# PR9018.net
KiCad netlist of a schematic drawn in EAGLE
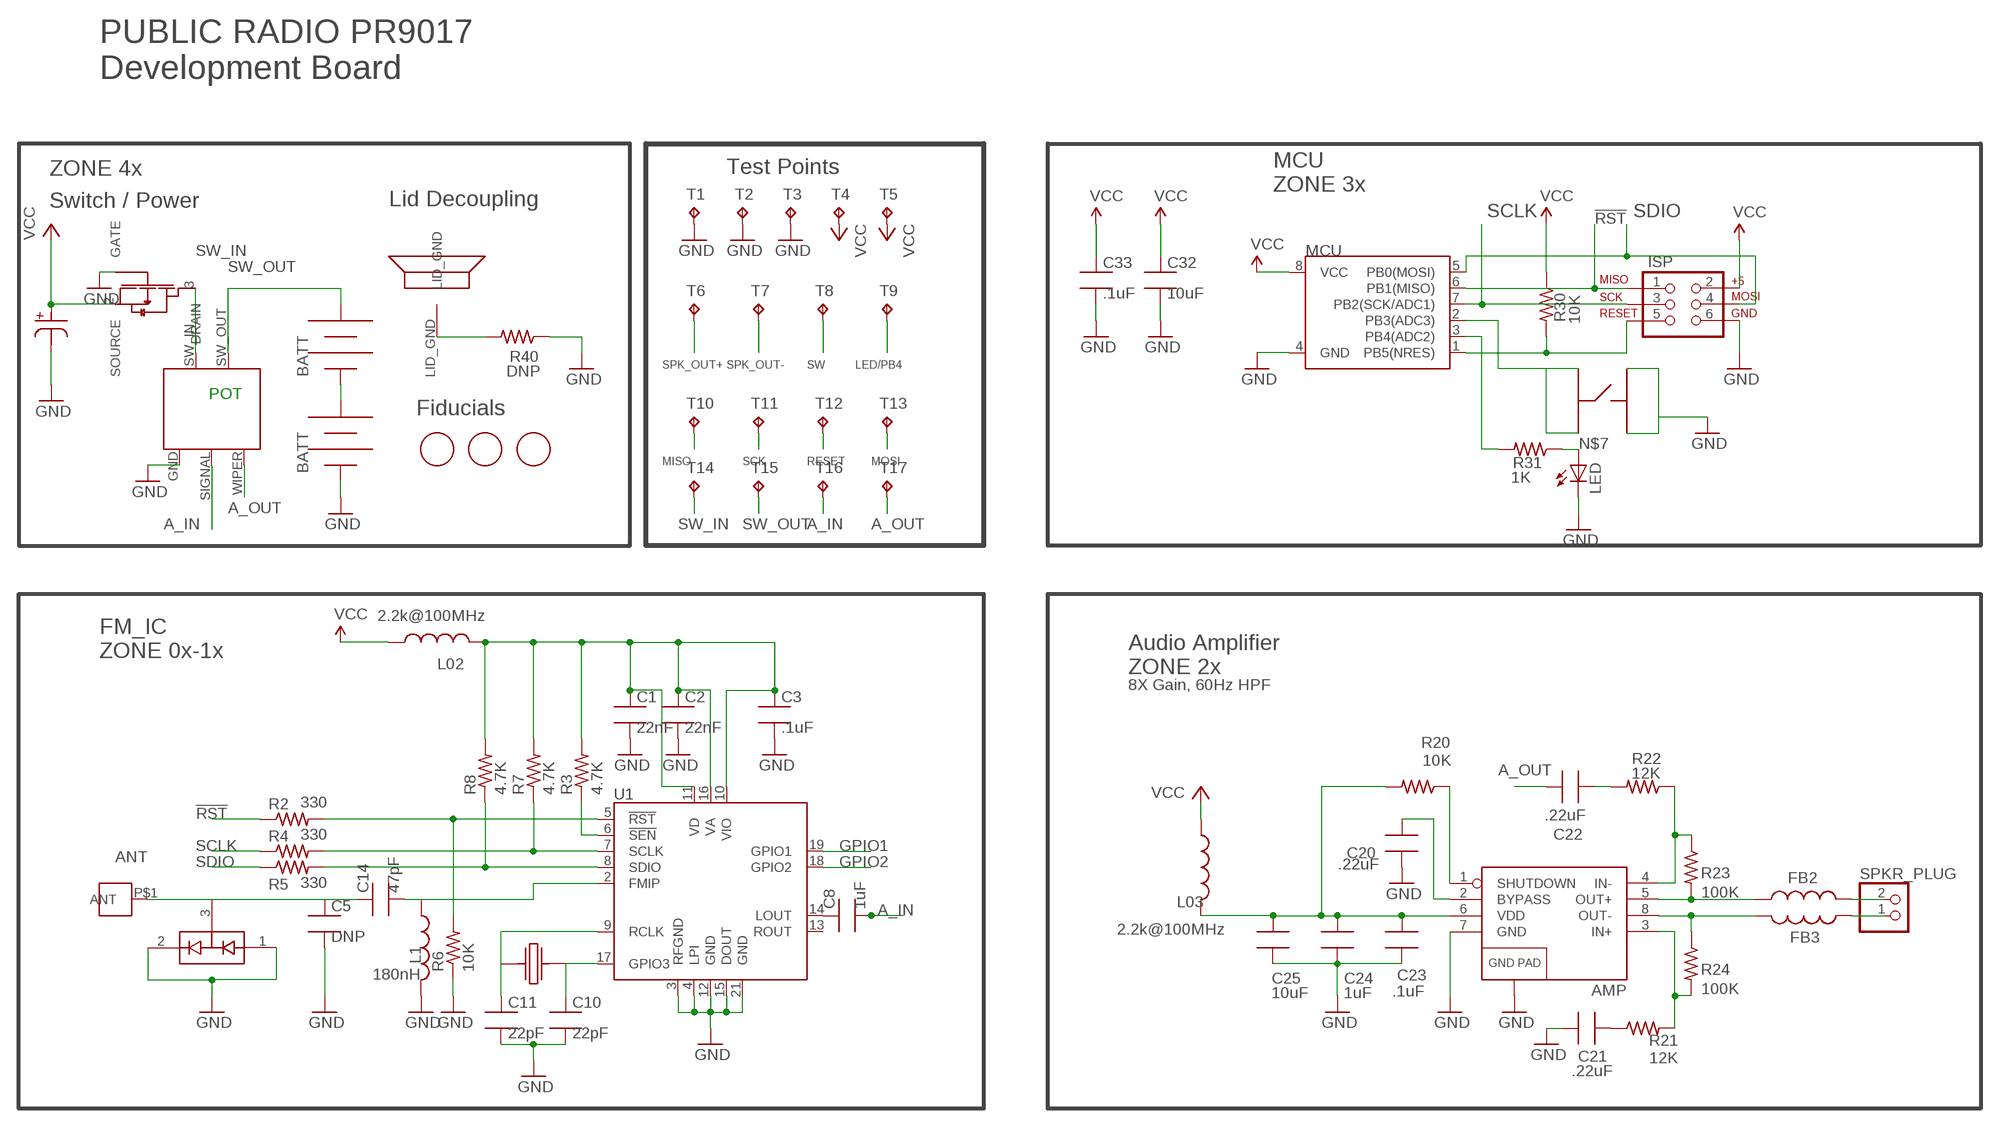
[diagram p0: schematic, sheet 1]

(export (version "E")
  (design (tool "Eeschema 10.0.6"))
  (components
    (comp (ref "AMP")
      (value "TPA6203A1")
      (footprint "eagle-import:8-MSOP")
      (libsource (lib "eagle-import") (part "TPA6203A1"))
    )
    (comp (ref "ANT_MOUNT")
      (value "DNP")
      (footprint "eagle-import:M3_BOLT_HOLE")
      (libsource (lib "eagle-import") (part "M3_SCREW_POST"))
    )
    (comp (ref "C1")
      (value "22nF")
      (footprint "eagle-import:0603_CPL")
      (fields
        (field (name "MFG_PN") "CL10B223KB8NNNC")
        (field (name "TOL") "10%")
        (field (name "VOLTAGE") "16V")
      )
      (libsource (lib "eagle-import") (part "C_SMT_0603_CPL"))
    )
    (comp (ref "C2")
      (value "22nF")
      (footprint "eagle-import:0603_CPL")
      (fields
        (field (name "MFG_PN") "CL10B223KB8NNNC")
        (field (name "TOL") "10%")
        (field (name "VOLTAGE") "16V")
      )
      (libsource (lib "eagle-import") (part "C_SMT_0603_CPL"))
    )
    (comp (ref "C3")
      (value ".1uF")
      (footprint "eagle-import:0603_CPL")
      (fields
        (field (name "MFG_PN") "CL10B104KB8SFNC")
        (field (name "TOL") "10%")
        (field (name "VOLTAGE") "16V")
      )
      (libsource (lib "eagle-import") (part "C_SMT_0603_CPL"))
    )
    (comp (ref "C5")
      (value "DNP")
      (footprint "eagle-import:0603_CPL")
      (fields (field (name "MFG_PN") "DNP") (field (name "TOL") "2%") (field (name "VOLTAGE") "50V"))
      (libsource (lib "eagle-import") (part "C_SMT_0603_CPL"))
    )
    (comp (ref "C8")
      (value "1uF")
      (footprint "eagle-import:0603_CPL")
      (fields
        (field (name "MFG_PN") "CL10B105KP8NNNC")
        (field (name "TOL") "10%")
        (field (name "VOLTAGE") "10V")
      )
      (libsource (lib "eagle-import") (part "C_SMT_0603_CPL"))
    )
    (comp (ref "C10")
      (value "22pF")
      (footprint "eagle-import:0603_CPL")
      (fields
        (field (name "MFG_PN") "C1608C0G1H220J080AA")
        (field (name "TOL") "5%")
        (field (name "VOLTAGE") "50V")
      )
      (libsource (lib "eagle-import") (part "C_SMT_0603_CPL"))
    )
    (comp (ref "C11")
      (value "22pF")
      (footprint "eagle-import:0603_CPL")
      (fields
        (field (name "MFG_PN") "C1608C0G1H220J080AA")
        (field (name "TOL") "5%")
        (field (name "VOLTAGE") "50V")
      )
      (libsource (lib "eagle-import") (part "C_SMT_0603_CPL"))
    )
    (comp (ref "C14")
      (value "47pF")
      (footprint "eagle-import:0603_CPL")
      (fields
        (field (name "MFG_PN") "CL10C470JB8NCNC")
        (field (name "TOL") "5%")
        (field (name "VOLTAGE") "50V")
      )
      (libsource (lib "eagle-import") (part "C_SMT_0603_CPL"))
    )
    (comp (ref "C20")
      (value ".22uF")
      (footprint "eagle-import:0603_CPL")
      (fields
        (field (name "MFG_PN") "C1608X7R1C224K080AC")
        (field (name "TOL") "10%")
        (field (name "VOLTAGE") "16V")
      )
      (libsource (lib "eagle-import") (part "C_SMT_0603_CPL"))
    )
    (comp (ref "C21")
      (value ".22uF")
      (footprint "eagle-import:0603_CPL")
      (fields
        (field (name "MFG_PN") "C1608X7R1C224K080AC")
        (field (name "TOL") "10%")
        (field (name "VOLTAGE") "16V")
      )
      (libsource (lib "eagle-import") (part "C_SMT_0603_CPL"))
    )
    (comp (ref "C22")
      (value ".22uF")
      (footprint "eagle-import:0603_CPL")
      (fields
        (field (name "MFG_PN") "C1608X7R1C224K080AC")
        (field (name "TOL") "10%")
        (field (name "VOLTAGE") "16V")
      )
      (libsource (lib "eagle-import") (part "C_SMT_0603_CPL"))
    )
    (comp (ref "C23")
      (value ".1uF")
      (footprint "eagle-import:0603_CPL")
      (fields
        (field (name "MFG_PN") "CL10B104KB8SFNC")
        (field (name "TOL") "10%")
        (field (name "VOLTAGE") "16V")
      )
      (libsource (lib "eagle-import") (part "C_SMT_0603_CPL"))
    )
    (comp (ref "C24")
      (value "1uF")
      (footprint "eagle-import:0603_CPL")
      (fields
        (field (name "MFG_PN") "CL10B105KP8NNNC")
        (field (name "TOL") "10%")
        (field (name "VOLTAGE") "10V")
      )
      (libsource (lib "eagle-import") (part "C_SMT_0603_CPL"))
    )
    (comp (ref "C25")
      (value "10uF")
      (footprint "eagle-import:0603_CPL")
      (fields
        (field (name "MFG_PN") "CL10A106MQ8NNNC")
        (field (name "TOL") "20%")
        (field (name "VOLTAGE") "6.3V")
      )
      (libsource (lib "eagle-import") (part "C_SMT_0603_CPL"))
    )
    (comp (ref "C32")
      (value "10uF")
      (footprint "eagle-import:0603_CPL")
      (fields
        (field (name "MFG_PN") "CL10A106MQ8NNNC")
        (field (name "TOL") "20%")
        (field (name "VOLTAGE") "6.3V")
      )
      (libsource (lib "eagle-import") (part "C_SMT_0603_CPL"))
    )
    (comp (ref "C33")
      (value ".1uF")
      (footprint "eagle-import:0603_CPL")
      (fields
        (field (name "MFG_PN") "CL10B104KB8SFNC")
        (field (name "TOL") "10%")
        (field (name "VOLTAGE") "16V")
      )
      (libsource (lib "eagle-import") (part "C_SMT_0603_CPL"))
    )
    (comp (ref "C40")
      (value "220uF")
      (footprint "eagle-import:NICHICON_UD_63")
      (fields (field (name "TOL") "20%") (field (name "VOLTAGE") "16V"))
      (libsource (lib "eagle-import") (part "NICHICON_SERIESUD"))
    )
    (comp (ref "D1")
      (value "BAV99")
      (footprint "eagle-import:SOT23_CPL")
      (fields (field (name "MFG_PN") "BAV99,215"))
      (libsource (lib "eagle-import") (part "BAV99"))
    )
    (comp (ref "FB2")
      (value "L_SMT_0805_ADAFRUIT")
      (footprint "eagle-import:0805_ADAFRUIT")
      (fields
        (field (name "CURRENT") "2A")
        (field (name "DCR") "45m")
        (field (name "MFG_PN") "HI0805R800R-10")
      )
      (libsource (lib "eagle-import") (part "L_SMT_0805_ADAFRUIT"))
    )
    (comp (ref "FB3")
      (value "L_SMT_0805_ADAFRUIT")
      (footprint "eagle-import:0805_ADAFRUIT")
      (fields
        (field (name "CURRENT") "2A")
        (field (name "DCR") "45m")
        (field (name "MFG_PN") "HI0805R800R-10")
      )
      (libsource (lib "eagle-import") (part "L_SMT_0805_ADAFRUIT"))
    )
    (comp (ref "FET1")
      (value "AO3435")
      (footprint "eagle-import:SOT23_CPL")
      (fields (field (name "MFG_PN") "AO3435"))
      (libsource (lib "eagle-import") (part "AO3435"))
    )
    (comp (ref "ISP")
      (value "AVR_SPI_PRG_6NS")
      (footprint "eagle-import:2X3-NS")
      (libsource (lib "eagle-import") (part "AVR_SPI_PRG_6NS"))
    )
    (comp (ref "JP5")
      (value "BK-92_MPD_AA_BATT_CLIP")
      (footprint "eagle-import:BK92_AA_BATT")
      (libsource (lib "eagle-import") (part "BK-92_MPD_AA_BATT_CLIP"))
    )
    (comp (ref "JP6")
      (value "BK-92_MPD_AA_BATT_CLIP")
      (footprint "eagle-import:BK92_AA_BATT")
      (libsource (lib "eagle-import") (part "BK-92_MPD_AA_BATT_CLIP"))
    )
    (comp (ref "L1")
      (value "180nH")
      (footprint "eagle-import:0805_ADAFRUIT")
      (fields
        (field (name "CURRENT") "400mA")
        (field (name "DCR") "640m")
        (field (name "MFG_PN") "AISC-0805-R18J-T")
        (field (name "TOL") "5%")
      )
      (libsource (lib "eagle-import") (part "L_SMT_0805_ADAFRUIT"))
    )
    (comp (ref "L02")
      (value "2.2k@100MHz")
      (footprint "eagle-import:0603_CPL")
      (fields
        (field (name "CURRENT") "150mA")
        (field (name "DCR") "2.3")
        (field (name "MFG_PN") "HZ0603A222R-10")
      )
      (libsource (lib "eagle-import") (part "L_SMT_0603_CPL"))
    )
    (comp (ref "L03")
      (value "2.2k@100MHz")
      (footprint "eagle-import:0603_CPL")
      (fields
        (field (name "CURRENT") "150mA")
        (field (name "DCR") "2.3")
        (field (name "MFG_PN") "HZ0603A222R-10")
      )
      (libsource (lib "eagle-import") (part "L_SMT_0603_CPL"))
    )
    (comp (ref "LED")
      (value "LED")
      (footprint "eagle-import:0603_CPL")
      (fields (field (name "MFG_PN") "LY R976-PS-36"))
      (libsource (lib "eagle-import") (part "LED"))
    )
    (comp (ref "MARK1")
      (value "FIDUCIAL")
      (footprint "eagle-import:FIDUCIAL_1MM")
      (libsource (lib "eagle-import") (part "FIDUCIAL"))
    )
    (comp (ref "MARK2")
      (value "FIDUCIAL")
      (footprint "eagle-import:FIDUCIAL_1MM")
      (libsource (lib "eagle-import") (part "FIDUCIAL"))
    )
    (comp (ref "MARK3")
      (value "FIDUCIAL")
      (footprint "eagle-import:FIDUCIAL_1MM")
      (libsource (lib "eagle-import") (part "FIDUCIAL"))
    )
    (comp (ref "MCU")
      (value "ATTINY45TINY45-20-SMT")
      (footprint "eagle-import:8-SOIC")
      (libsource (lib "eagle-import") (part "ATTINY45TINY45-20-SMT"))
    )
    (comp (ref "R1")
      (value "RV170SF_TAIWANA_POT_SW")
      (footprint "eagle-import:RV170SF_SW_POT")
      (libsource (lib "eagle-import") (part "RV170SF_TAIWANA_POT_SW"))
    )
    (comp (ref "R2")
      (value "330")
      (footprint "eagle-import:0603_CPL")
      (fields (field (name "MFG_PN") "MCR03ERTJ331") (field (name "POWER") "1/10W") (field (name "TOL") "5%"))
      (libsource (lib "eagle-import") (part "R_SMT_R0603_CPL"))
    )
    (comp (ref "R3")
      (value "4.7K")
      (footprint "eagle-import:0603_CPL")
      (fields
        (field (name "MFG_PN") "ERJ-3EKF4701V")
        (field (name "POWER") "1/10W")
        (field (name "TOL") "1%")
      )
      (libsource (lib "eagle-import") (part "R_SMT_R0603_CPL"))
    )
    (comp (ref "R4")
      (value "330")
      (footprint "eagle-import:0603_CPL")
      (fields (field (name "MFG_PN") "MCR03ERTJ331") (field (name "POWER") "1/10W") (field (name "TOL") "5%"))
      (libsource (lib "eagle-import") (part "R_SMT_R0603_CPL"))
    )
    (comp (ref "R5")
      (value "330")
      (footprint "eagle-import:0603_CPL")
      (fields (field (name "MFG_PN") "MCR03ERTJ331") (field (name "POWER") "1/10W") (field (name "TOL") "5%"))
      (libsource (lib "eagle-import") (part "R_SMT_R0603_CPL"))
    )
    (comp (ref "R6")
      (value "10K")
      (footprint "eagle-import:0603_CPL")
      (fields
        (field (name "MFG_PN") "ERJ-3GEYJ103V")
        (field (name "POWER") "1/10W")
        (field (name "TOL") "5%")
      )
      (libsource (lib "eagle-import") (part "R_SMT_R0603_CPL"))
    )
    (comp (ref "R7")
      (value "4.7K")
      (footprint "eagle-import:0603_CPL")
      (fields
        (field (name "MFG_PN") "ERJ-3EKF4701V")
        (field (name "POWER") "1/10W")
        (field (name "TOL") "1%")
      )
      (libsource (lib "eagle-import") (part "R_SMT_R0603_CPL"))
    )
    (comp (ref "R8")
      (value "4.7K")
      (footprint "eagle-import:0603_CPL")
      (fields
        (field (name "MFG_PN") "ERJ-3EKF4701V")
        (field (name "POWER") "1/10W")
        (field (name "TOL") "1%")
      )
      (libsource (lib "eagle-import") (part "R_SMT_R0603_CPL"))
    )
    (comp (ref "R20")
      (value "10K")
      (footprint "eagle-import:0603_CPL")
      (fields
        (field (name "MFG_PN") "ERJ-3GEYJ103V")
        (field (name "POWER") "1/10W")
        (field (name "TOL") "5%")
      )
      (libsource (lib "eagle-import") (part "R_SMT_R0603_CPL"))
    )
    (comp (ref "R21")
      (value "12K")
      (footprint "eagle-import:0603_CPL")
      (fields
        (field (name "MFG_PN") "RC0603FR-0712KL")
        (field (name "POWER") "1/10W")
        (field (name "TOL") "1%")
      )
      (libsource (lib "eagle-import") (part "R_SMT_R0603_CPL"))
    )
    (comp (ref "R22")
      (value "12K")
      (footprint "eagle-import:0603_CPL")
      (fields
        (field (name "MFG_PN") "RC0603FR-0712KL")
        (field (name "POWER") "1/10W")
        (field (name "TOL") "1%")
      )
      (libsource (lib "eagle-import") (part "R_SMT_R0603_CPL"))
    )
    (comp (ref "R23")
      (value "100K")
      (footprint "eagle-import:0603_CPL")
      (fields
        (field (name "MFG_PN") "ERJ-3EKF1003V")
        (field (name "POWER") "1/10W")
        (field (name "TOL") "1%")
      )
      (libsource (lib "eagle-import") (part "R_SMT_R0603_CPL"))
    )
    (comp (ref "R24")
      (value "100K")
      (footprint "eagle-import:0603_CPL")
      (fields
        (field (name "MFG_PN") "ERJ-3EKF1003V")
        (field (name "POWER") "1/10W")
        (field (name "TOL") "1%")
      )
      (libsource (lib "eagle-import") (part "R_SMT_R0603_CPL"))
    )
    (comp (ref "R30")
      (value "10K")
      (footprint "eagle-import:0603_CPL")
      (fields
        (field (name "MFG_PN") "ERJ-3GEYJ103V")
        (field (name "POWER") "1/10W")
        (field (name "TOL") "5%")
      )
      (libsource (lib "eagle-import") (part "R_SMT_R0603_CPL"))
    )
    (comp (ref "R31")
      (value "1K")
      (footprint "eagle-import:0603_CPL")
      (fields
        (field (name "MFG_PN") "ERJ-3EKF1001V")
        (field (name "POWER") "1/10W")
        (field (name "TOL") "1%")
      )
      (libsource (lib "eagle-import") (part "R_SMT_R0603_CPL"))
    )
    (comp (ref "R40")
      (value "DNP")
      (footprint "eagle-import:0603_CPL")
      (fields (field (name "MFG_PN") "ERJ-3GEY0R00V"))
      (libsource (lib "eagle-import") (part "R_SMT_R0603_CPL"))
    )
    (comp (ref "SPKR_PLACE")
      (value "DNP")
      (footprint "eagle-import:PR2023_SPKR_PLACE")
      (libsource (lib "eagle-import") (part "PR2023_SPKR"))
    )
    (comp (ref "SPKR_PLUG")
      (value "JST_2PIN-SMT-RA")
      (footprint "eagle-import:JST-B2B-PH-SM4-TB")
      (libsource (lib "eagle-import") (part "JST_2PIN-SMT-RA"))
    )
    (comp (ref "SW1")
      (value "C&K_PTS645")
      (footprint "eagle-import:C&K_PTS645_SMT")
      (libsource (lib "eagle-import") (part "C&K_PTS645"))
    )
    (comp (ref "T1")
      (value "TPTP20R")
      (footprint "eagle-import:TP20R")
      (libsource (lib "eagle-import") (part "TPTP20R"))
    )
    (comp (ref "T2")
      (value "TPTP20R")
      (footprint "eagle-import:TP20R")
      (libsource (lib "eagle-import") (part "TPTP20R"))
    )
    (comp (ref "T3")
      (value "TPTP20R")
      (footprint "eagle-import:TP20R")
      (libsource (lib "eagle-import") (part "TPTP20R"))
    )
    (comp (ref "T4")
      (value "TPTP20R")
      (footprint "eagle-import:TP20R")
      (libsource (lib "eagle-import") (part "TPTP20R"))
    )
    (comp (ref "T5")
      (value "TPTP20R")
      (footprint "eagle-import:TP20R")
      (libsource (lib "eagle-import") (part "TPTP20R"))
    )
    (comp (ref "T6")
      (value "TPTP20R")
      (footprint "eagle-import:TP20R")
      (libsource (lib "eagle-import") (part "TPTP20R"))
    )
    (comp (ref "T7")
      (value "TPTP20R")
      (footprint "eagle-import:TP20R")
      (libsource (lib "eagle-import") (part "TPTP20R"))
    )
    (comp (ref "T8")
      (value "TPTP20R")
      (footprint "eagle-import:TP20R")
      (libsource (lib "eagle-import") (part "TPTP20R"))
    )
    (comp (ref "T9")
      (value "TPTP20R")
      (footprint "eagle-import:TP20R")
      (libsource (lib "eagle-import") (part "TPTP20R"))
    )
    (comp (ref "T10")
      (value "TPTP20R")
      (footprint "eagle-import:TP20R")
      (libsource (lib "eagle-import") (part "TPTP20R"))
    )
    (comp (ref "T11")
      (value "TPTP20R")
      (footprint "eagle-import:TP20R")
      (libsource (lib "eagle-import") (part "TPTP20R"))
    )
    (comp (ref "T12")
      (value "TPTP20R")
      (footprint "eagle-import:TP20R")
      (libsource (lib "eagle-import") (part "TPTP20R"))
    )
    (comp (ref "T13")
      (value "TPTP20R")
      (footprint "eagle-import:TP20R")
      (libsource (lib "eagle-import") (part "TPTP20R"))
    )
    (comp (ref "T14")
      (value "TPTP20R")
      (footprint "eagle-import:TP20R")
      (libsource (lib "eagle-import") (part "TPTP20R"))
    )
    (comp (ref "T15")
      (value "TPTP20R")
      (footprint "eagle-import:TP20R")
      (libsource (lib "eagle-import") (part "TPTP20R"))
    )
    (comp (ref "T16")
      (value "TPTP20R")
      (footprint "eagle-import:TP20R")
      (libsource (lib "eagle-import") (part "TPTP20R"))
    )
    (comp (ref "T17")
      (value "TPTP20R")
      (footprint "eagle-import:TP20R")
      (libsource (lib "eagle-import") (part "TPTP20R"))
    )
    (comp (ref "U1")
      (value "SI4702-C19-GMR")
      (footprint "eagle-import:SI470X_20_QFN")
      (libsource (lib "eagle-import") (part "SI4702-C19-GMR"))
    )
    (comp (ref "X1")
      (value "ABS25XTAL")
      (footprint "eagle-import:4-SOJ")
      (libsource (lib "eagle-import") (part "ABS25XTAL"))
    )
  )
  (nets
    (net (code "1") (name "/ANT") (class "Default")
      (node (ref "ANT_MOUNT") (pin "P$1") (pinfunction "ANT_P$1") (pintype "bidirectional"))
      (node (ref "C14") (pin "1") (pinfunction "1_1") (pintype "passive"))
      (node (ref "C5") (pin "1") (pinfunction "1_1") (pintype "passive"))
      (node (ref "D1") (pin "3") (pinfunction "COM_3") (pintype "bidirectional"))
    )
    (net (code "2") (name "/A_IN") (class "Default")
      (node (ref "C8") (pin "2") (pinfunction "2_2") (pintype "passive"))
      (node (ref "R1") (pin "SIGNAL") (pinfunction "SIGNAL_SIGNAL") (pintype "bidirectional"))
      (node (ref "T16") (pin "TP") (pinfunction "TP_TP") (pintype "input"))
    )
    (net (code "3") (name "/A_OUT") (class "Default")
      (node (ref "C22") (pin "2") (pinfunction "2_2") (pintype "passive"))
      (node (ref "R1") (pin "WIPER") (pinfunction "WIPER_WIPER") (pintype "bidirectional"))
      (node (ref "T17") (pin "TP") (pinfunction "TP_TP") (pintype "input"))
    )
    (net (code "4") (name "/GPIO1") (class "Default")
      (node (ref "U1") (pin "19") (pinfunction "GPIO1_19") (pintype "bidirectional"))
    )
    (net (code "5") (name "/GPIO2") (class "Default")
      (node (ref "U1") (pin "18") (pinfunction "GPIO2_18") (pintype "bidirectional"))
    )
    (net (code "6") (name "/LED{slash}PB4") (class "Default")
      (node (ref "MCU") (pin "3") (pinfunction "PB4(ADC2)_3") (pintype "bidirectional"))
      (node (ref "R31") (pin "2") (pinfunction "2_2") (pintype "passive"))
      (node (ref "T9") (pin "TP") (pinfunction "TP_TP") (pintype "input"))
    )
    (net (code "7") (name "/N$7") (class "Default")
      (node (ref "LED") (pin "1") (pinfunction "A_1") (pintype "passive"))
      (node (ref "R31") (pin "1") (pinfunction "1_1") (pintype "passive"))
    )
    (net (code "8") (name "/RESET") (class "Default")
      (node (ref "ISP") (pin "5") (pinfunction "5_5") (pintype "passive"))
      (node (ref "MCU") (pin "1") (pinfunction "PB5(NRES)_1") (pintype "bidirectional"))
      (node (ref "R30") (pin "2") (pinfunction "2_2") (pintype "passive"))
      (node (ref "T12") (pin "TP") (pinfunction "TP_TP") (pintype "input"))
    )
    (net (code "9") (name "/SCLK") (class "Default")
      (node (ref "ISP") (pin "3") (pinfunction "3_3") (pintype "passive"))
      (node (ref "MCU") (pin "7") (pinfunction "PB2(SCK/ADC1)_7") (pintype "bidirectional"))
      (node (ref "R4") (pin "1") (pinfunction "1_1") (pintype "passive"))
      (node (ref "T11") (pin "TP") (pinfunction "TP_TP") (pintype "input"))
    )
    (net (code "10") (name "/SDIO") (class "Default")
      (node (ref "ISP") (pin "4") (pinfunction "4_4") (pintype "passive"))
      (node (ref "MCU") (pin "5") (pinfunction "PB0(MOSI)_5") (pintype "bidirectional"))
      (node (ref "R5") (pin "1") (pinfunction "1_1") (pintype "passive"))
      (node (ref "T13") (pin "TP") (pinfunction "TP_TP") (pintype "input"))
    )
    (net (code "11") (name "/SPK_OUT+") (class "Default")
      (node (ref "FB2") (pin "2") (pinfunction "2_2") (pintype "passive"))
      (node (ref "SPKR_PLUG") (pin "2") (pinfunction "1_2") (pintype "passive"))
      (node (ref "T6") (pin "TP") (pinfunction "TP_TP") (pintype "input"))
    )
    (net (code "12") (name "/SPK_OUT-") (class "Default")
      (node (ref "FB3") (pin "1") (pinfunction "1_1") (pintype "passive"))
      (node (ref "SPKR_PLUG") (pin "1") (pinfunction "2_1") (pintype "passive"))
      (node (ref "T7") (pin "TP") (pinfunction "TP_TP") (pintype "input"))
    )
    (net (code "13") (name "/SW") (class "Default")
      (node (ref "MCU") (pin "2") (pinfunction "PB3(ADC3)_2") (pintype "bidirectional"))
      (node (ref "SW1") (pin "P$3") (pinfunction "P$3_P$3") (pintype "bidirectional"))
      (node (ref "SW1") (pin "P$4") (pinfunction "P$4_P$4") (pintype "bidirectional"))
      (node (ref "T8") (pin "TP") (pinfunction "TP_TP") (pintype "input"))
    )
    (net (code "14") (name "/SW_IN") (class "Default")
      (node (ref "FET1") (pin "3") (pinfunction "DRAIN_3") (pintype "bidirectional"))
      (node (ref "R1") (pin "SW_IN") (pinfunction "SW_IN_SW_IN") (pintype "bidirectional"))
      (node (ref "T14") (pin "TP") (pinfunction "TP_TP") (pintype "input"))
    )
    (net (code "15") (name "/SW_OUT") (class "Default")
      (node (ref "JP5") (pin "POS") (pinfunction "POS_POS") (pintype "bidirectional"))
      (node (ref "JP5") (pin "POS@2") (pinfunction "POS_POS@2") (pintype "bidirectional"))
      (node (ref "R1") (pin "SW_OUT") (pinfunction "SW_OUT_SW_OUT") (pintype "bidirectional"))
      (node (ref "T15") (pin "TP") (pinfunction "TP_TP") (pintype "input"))
    )
    (net (code "16") (name "/~{RST}") (class "Default")
      (node (ref "ISP") (pin "1") (pinfunction "1_1") (pintype "passive"))
      (node (ref "MCU") (pin "6") (pinfunction "PB1(MISO)_6") (pintype "bidirectional"))
      (node (ref "R2") (pin "1") (pinfunction "1_1") (pintype "passive"))
      (node (ref "T10") (pin "TP") (pinfunction "TP_TP") (pintype "input"))
    )
    (net (code "17") (name "GND") (class "Default")
      (node (ref "AMP") (pin "7") (pinfunction "GND_7") (pintype "power_in"))
      (node (ref "AMP") (pin "9") (pinfunction "GND_9") (pintype "power_in"))
      (node (ref "C1") (pin "2") (pinfunction "2_2") (pintype "passive"))
      (node (ref "C10") (pin "2") (pinfunction "2_2") (pintype "passive"))
      (node (ref "C11") (pin "2") (pinfunction "2_2") (pintype "passive"))
      (node (ref "C2") (pin "2") (pinfunction "2_2") (pintype "passive"))
      (node (ref "C20") (pin "1") (pinfunction "1_1") (pintype "passive"))
      (node (ref "C21") (pin "1") (pinfunction "1_1") (pintype "passive"))
      (node (ref "C23") (pin "2") (pinfunction "2_2") (pintype "passive"))
      (node (ref "C24") (pin "2") (pinfunction "2_2") (pintype "passive"))
      (node (ref "C25") (pin "2") (pinfunction "2_2") (pintype "passive"))
      (node (ref "C3") (pin "2") (pinfunction "2_2") (pintype "passive"))
      (node (ref "C32") (pin "2") (pinfunction "2_2") (pintype "passive"))
      (node (ref "C33") (pin "2") (pinfunction "2_2") (pintype "passive"))
      (node (ref "C40") (pin "P$2") (pinfunction "P$2_P$2") (pintype "bidirectional"))
      (node (ref "C5") (pin "2") (pinfunction "2_2") (pintype "passive"))
      (node (ref "D1") (pin "1") (pinfunction "A1_1") (pintype "bidirectional"))
      (node (ref "D1") (pin "2") (pinfunction "C2_2") (pintype "bidirectional"))
      (node (ref "FET1") (pin "1") (pinfunction "GATE_1") (pintype "bidirectional"))
      (node (ref "ISP") (pin "6") (pinfunction "6_6") (pintype "passive"))
      (node (ref "JP6") (pin "NEG") (pinfunction "NEG_NEG") (pintype "bidirectional"))
      (node (ref "JP6") (pin "NEG@2") (pinfunction "NEG_NEG@2") (pintype "bidirectional"))
      (node (ref "L1") (pin "2") (pinfunction "2_2") (pintype "passive"))
      (node (ref "LED") (pin "2") (pinfunction "C_2") (pintype "passive"))
      (node (ref "MCU") (pin "4") (pinfunction "GND_4") (pintype "bidirectional"))
      (node (ref "R1") (pin "GND") (pinfunction "GND_GND") (pintype "bidirectional"))
      (node (ref "R40") (pin "1") (pinfunction "1_1") (pintype "passive"))
      (node (ref "R6") (pin "1") (pinfunction "1_1") (pintype "passive"))
      (node (ref "SW1") (pin "P$1") (pinfunction "P$1_P$1") (pintype "bidirectional"))
      (node (ref "SW1") (pin "P$2") (pinfunction "P$2_P$2") (pintype "bidirectional"))
      (node (ref "T1") (pin "TP") (pinfunction "TP_TP") (pintype "input"))
      (node (ref "T2") (pin "TP") (pinfunction "TP_TP") (pintype "input"))
      (node (ref "T3") (pin "TP") (pinfunction "TP_TP") (pintype "input"))
      (node (ref "U1") (pin "12") (pinfunction "GND_12") (pintype "bidirectional"))
      (node (ref "U1") (pin "15") (pinfunction "DOUT_15") (pintype "bidirectional"))
      (node (ref "U1") (pin "21") (pinfunction "GND_21") (pintype "bidirectional"))
      (node (ref "U1") (pin "3") (pinfunction "RFGND_3") (pintype "bidirectional"))
      (node (ref "U1") (pin "4") (pinfunction "LPI_4") (pintype "bidirectional"))
    )
    (net (code "18") (name "Net-(AMP-BYPASS)") (class "Default")
      (node (ref "AMP") (pin "2") (pinfunction "BYPASS_2") (pintype "bidirectional"))
      (node (ref "C20") (pin "2") (pinfunction "2_2") (pintype "passive"))
    )
    (net (code "19") (name "Net-(AMP-IN+)") (class "Default")
      (node (ref "AMP") (pin "3") (pinfunction "IN+_3") (pintype "bidirectional"))
      (node (ref "R21") (pin "2") (pinfunction "2_2") (pintype "passive"))
      (node (ref "R24") (pin "2") (pinfunction "2_2") (pintype "passive"))
    )
    (net (code "20") (name "Net-(AMP-IN-)") (class "Default")
      (node (ref "AMP") (pin "4") (pinfunction "IN-_4") (pintype "bidirectional"))
      (node (ref "R22") (pin "1") (pinfunction "1_1") (pintype "passive"))
      (node (ref "R23") (pin "1") (pinfunction "1_1") (pintype "passive"))
    )
    (net (code "21") (name "Net-(AMP-OUT+)") (class "Default")
      (node (ref "AMP") (pin "5") (pinfunction "OUT+_5") (pintype "bidirectional"))
      (node (ref "FB2") (pin "1") (pinfunction "1_1") (pintype "passive"))
      (node (ref "R23") (pin "2") (pinfunction "2_2") (pintype "passive"))
    )
    (net (code "22") (name "Net-(AMP-OUT-)") (class "Default")
      (node (ref "AMP") (pin "8") (pinfunction "OUT-_8") (pintype "bidirectional"))
      (node (ref "FB3") (pin "2") (pinfunction "2_2") (pintype "passive"))
      (node (ref "R24") (pin "1") (pinfunction "1_1") (pintype "passive"))
    )
    (net (code "23") (name "Net-(AMP-SHUTDOWN)") (class "Default")
      (node (ref "AMP") (pin "1") (pinfunction "SHUTDOWN_1") (pintype "input"))
      (node (ref "R20") (pin "1") (pinfunction "1_1") (pintype "passive"))
    )
    (net (code "24") (name "Net-(AMP-VDD)") (class "Default")
      (node (ref "AMP") (pin "6") (pinfunction "VDD_6") (pintype "power_in"))
      (node (ref "C23") (pin "1") (pinfunction "1_1") (pintype "passive"))
      (node (ref "C24") (pin "1") (pinfunction "1_1") (pintype "passive"))
      (node (ref "C25") (pin "1") (pinfunction "1_1") (pintype "passive"))
      (node (ref "L03") (pin "2") (pinfunction "2_2") (pintype "passive"))
      (node (ref "R20") (pin "2") (pinfunction "2_2") (pintype "passive"))
    )
    (net (code "25") (name "Net-(C21-Pad2)") (class "Default")
      (node (ref "C21") (pin "2") (pinfunction "2_2") (pintype "passive"))
      (node (ref "R21") (pin "1") (pinfunction "1_1") (pintype "passive"))
    )
    (net (code "26") (name "Net-(C22-Pad1)") (class "Default")
      (node (ref "C22") (pin "1") (pinfunction "1_1") (pintype "passive"))
      (node (ref "R22") (pin "2") (pinfunction "2_2") (pintype "passive"))
    )
    (net (code "27") (name "Net-(JP5-NEG-PadNEG@2)") (class "Default")
      (node (ref "JP5") (pin "NEG") (pinfunction "NEG_NEG") (pintype "bidirectional"))
      (node (ref "JP5") (pin "NEG@2") (pinfunction "NEG_NEG@2") (pintype "bidirectional"))
      (node (ref "JP6") (pin "POS") (pinfunction "POS_POS") (pintype "bidirectional"))
      (node (ref "JP6") (pin "POS@2") (pinfunction "POS_POS@2") (pintype "bidirectional"))
    )
    (net (code "28") (name "Net-(R40-Pad2)") (class "Default")
      (node (ref "R40") (pin "2") (pinfunction "2_2") (pintype "passive"))
      (node (ref "SPKR_PLACE") (pin "LID_GND") (pinfunction "LID_GND_LID_GND") (pintype "bidirectional"))
    )
    (net (code "29") (name "Net-(U1-FMIP)") (class "Default")
      (node (ref "C14") (pin "2") (pinfunction "2_2") (pintype "passive"))
      (node (ref "L1") (pin "1") (pinfunction "1_1") (pintype "passive"))
      (node (ref "U1") (pin "2") (pinfunction "FMIP_2") (pintype "bidirectional"))
    )
    (net (code "30") (name "Net-(U1-GPIO3)") (class "Default")
      (node (ref "C10") (pin "1") (pinfunction "1_1") (pintype "passive"))
      (node (ref "U1") (pin "17") (pinfunction "GPIO3_17") (pintype "bidirectional"))
      (node (ref "X1") (pin "P$4") (pinfunction "P$4_P$4") (pintype "bidirectional"))
    )
    (net (code "31") (name "Net-(U1-LOUT)") (class "Default")
      (node (ref "C8") (pin "1") (pinfunction "1_1") (pintype "passive"))
      (node (ref "U1") (pin "14") (pinfunction "LOUT_14") (pintype "bidirectional"))
    )
    (net (code "32") (name "Net-(U1-RCLK)") (class "Default")
      (node (ref "C11") (pin "1") (pinfunction "1_1") (pintype "passive"))
      (node (ref "U1") (pin "9") (pinfunction "RCLK_9") (pintype "bidirectional"))
      (node (ref "X1") (pin "P$1") (pinfunction "P$1_P$1") (pintype "bidirectional"))
    )
    (net (code "33") (name "Net-(U1-SCLK)") (class "Default")
      (node (ref "R4") (pin "2") (pinfunction "2_2") (pintype "passive"))
      (node (ref "R7") (pin "1") (pinfunction "1_1") (pintype "passive"))
      (node (ref "U1") (pin "7") (pinfunction "SCLK_7") (pintype "bidirectional"))
    )
    (net (code "34") (name "Net-(U1-SDIO)") (class "Default")
      (node (ref "R5") (pin "2") (pinfunction "2_2") (pintype "passive"))
      (node (ref "R8") (pin "1") (pinfunction "1_1") (pintype "passive"))
      (node (ref "U1") (pin "8") (pinfunction "SDIO_8") (pintype "bidirectional"))
    )
    (net (code "35") (name "Net-(U1-VA)") (class "Default")
      (node (ref "C1") (pin "1") (pinfunction "1_1") (pintype "passive"))
      (node (ref "C2") (pin "1") (pinfunction "1_1") (pintype "passive"))
      (node (ref "C3") (pin "1") (pinfunction "1_1") (pintype "passive"))
      (node (ref "L02") (pin "2") (pinfunction "2_2") (pintype "passive"))
      (node (ref "R3") (pin "2") (pinfunction "2_2") (pintype "passive"))
      (node (ref "R7") (pin "2") (pinfunction "2_2") (pintype "passive"))
      (node (ref "R8") (pin "2") (pinfunction "2_2") (pintype "passive"))
      (node (ref "U1") (pin "10") (pinfunction "VIO_10") (pintype "bidirectional"))
      (node (ref "U1") (pin "11") (pinfunction "VD_11") (pintype "bidirectional"))
      (node (ref "U1") (pin "16") (pinfunction "VA_16") (pintype "bidirectional"))
    )
    (net (code "36") (name "Net-(U1-~{RST})") (class "Default")
      (node (ref "R2") (pin "2") (pinfunction "2_2") (pintype "passive"))
      (node (ref "R6") (pin "2") (pinfunction "2_2") (pintype "passive"))
      (node (ref "U1") (pin "5") (pinfunction "~{RST}_5") (pintype "bidirectional"))
    )
    (net (code "37") (name "Net-(U1-~{SEN})") (class "Default")
      (node (ref "R3") (pin "1") (pinfunction "1_1") (pintype "passive"))
      (node (ref "U1") (pin "6") (pinfunction "~{SEN}_6") (pintype "bidirectional"))
    )
    (net (code "38") (name "VCC") (class "Default")
      (node (ref "C32") (pin "1") (pinfunction "1_1") (pintype "passive"))
      (node (ref "C33") (pin "1") (pinfunction "1_1") (pintype "passive"))
      (node (ref "C40") (pin "P$1") (pinfunction "P$1_P$1") (pintype "bidirectional"))
      (node (ref "FET1") (pin "2") (pinfunction "SOURCE_2") (pintype "bidirectional"))
      (node (ref "ISP") (pin "2") (pinfunction "2_2") (pintype "passive"))
      (node (ref "L02") (pin "1") (pinfunction "1_1") (pintype "passive"))
      (node (ref "L03") (pin "1") (pinfunction "1_1") (pintype "passive"))
      (node (ref "MCU") (pin "8") (pinfunction "VCC_8") (pintype "bidirectional"))
      (node (ref "R30") (pin "1") (pinfunction "1_1") (pintype "passive"))
      (node (ref "T4") (pin "TP") (pinfunction "TP_TP") (pintype "input"))
      (node (ref "T5") (pin "TP") (pinfunction "TP_TP") (pintype "input"))
    )
    (net (code "39") (name "unconnected-(U1-ROUT-Pad13)") (class "Default")
      (node (ref "U1") (pin "13") (pinfunction "ROUT_13") (pintype "bidirectional"))
    )
  )
)
